# 3_InfoPerif.net
KiCad netlist of a schematic drawn in Altium Designer
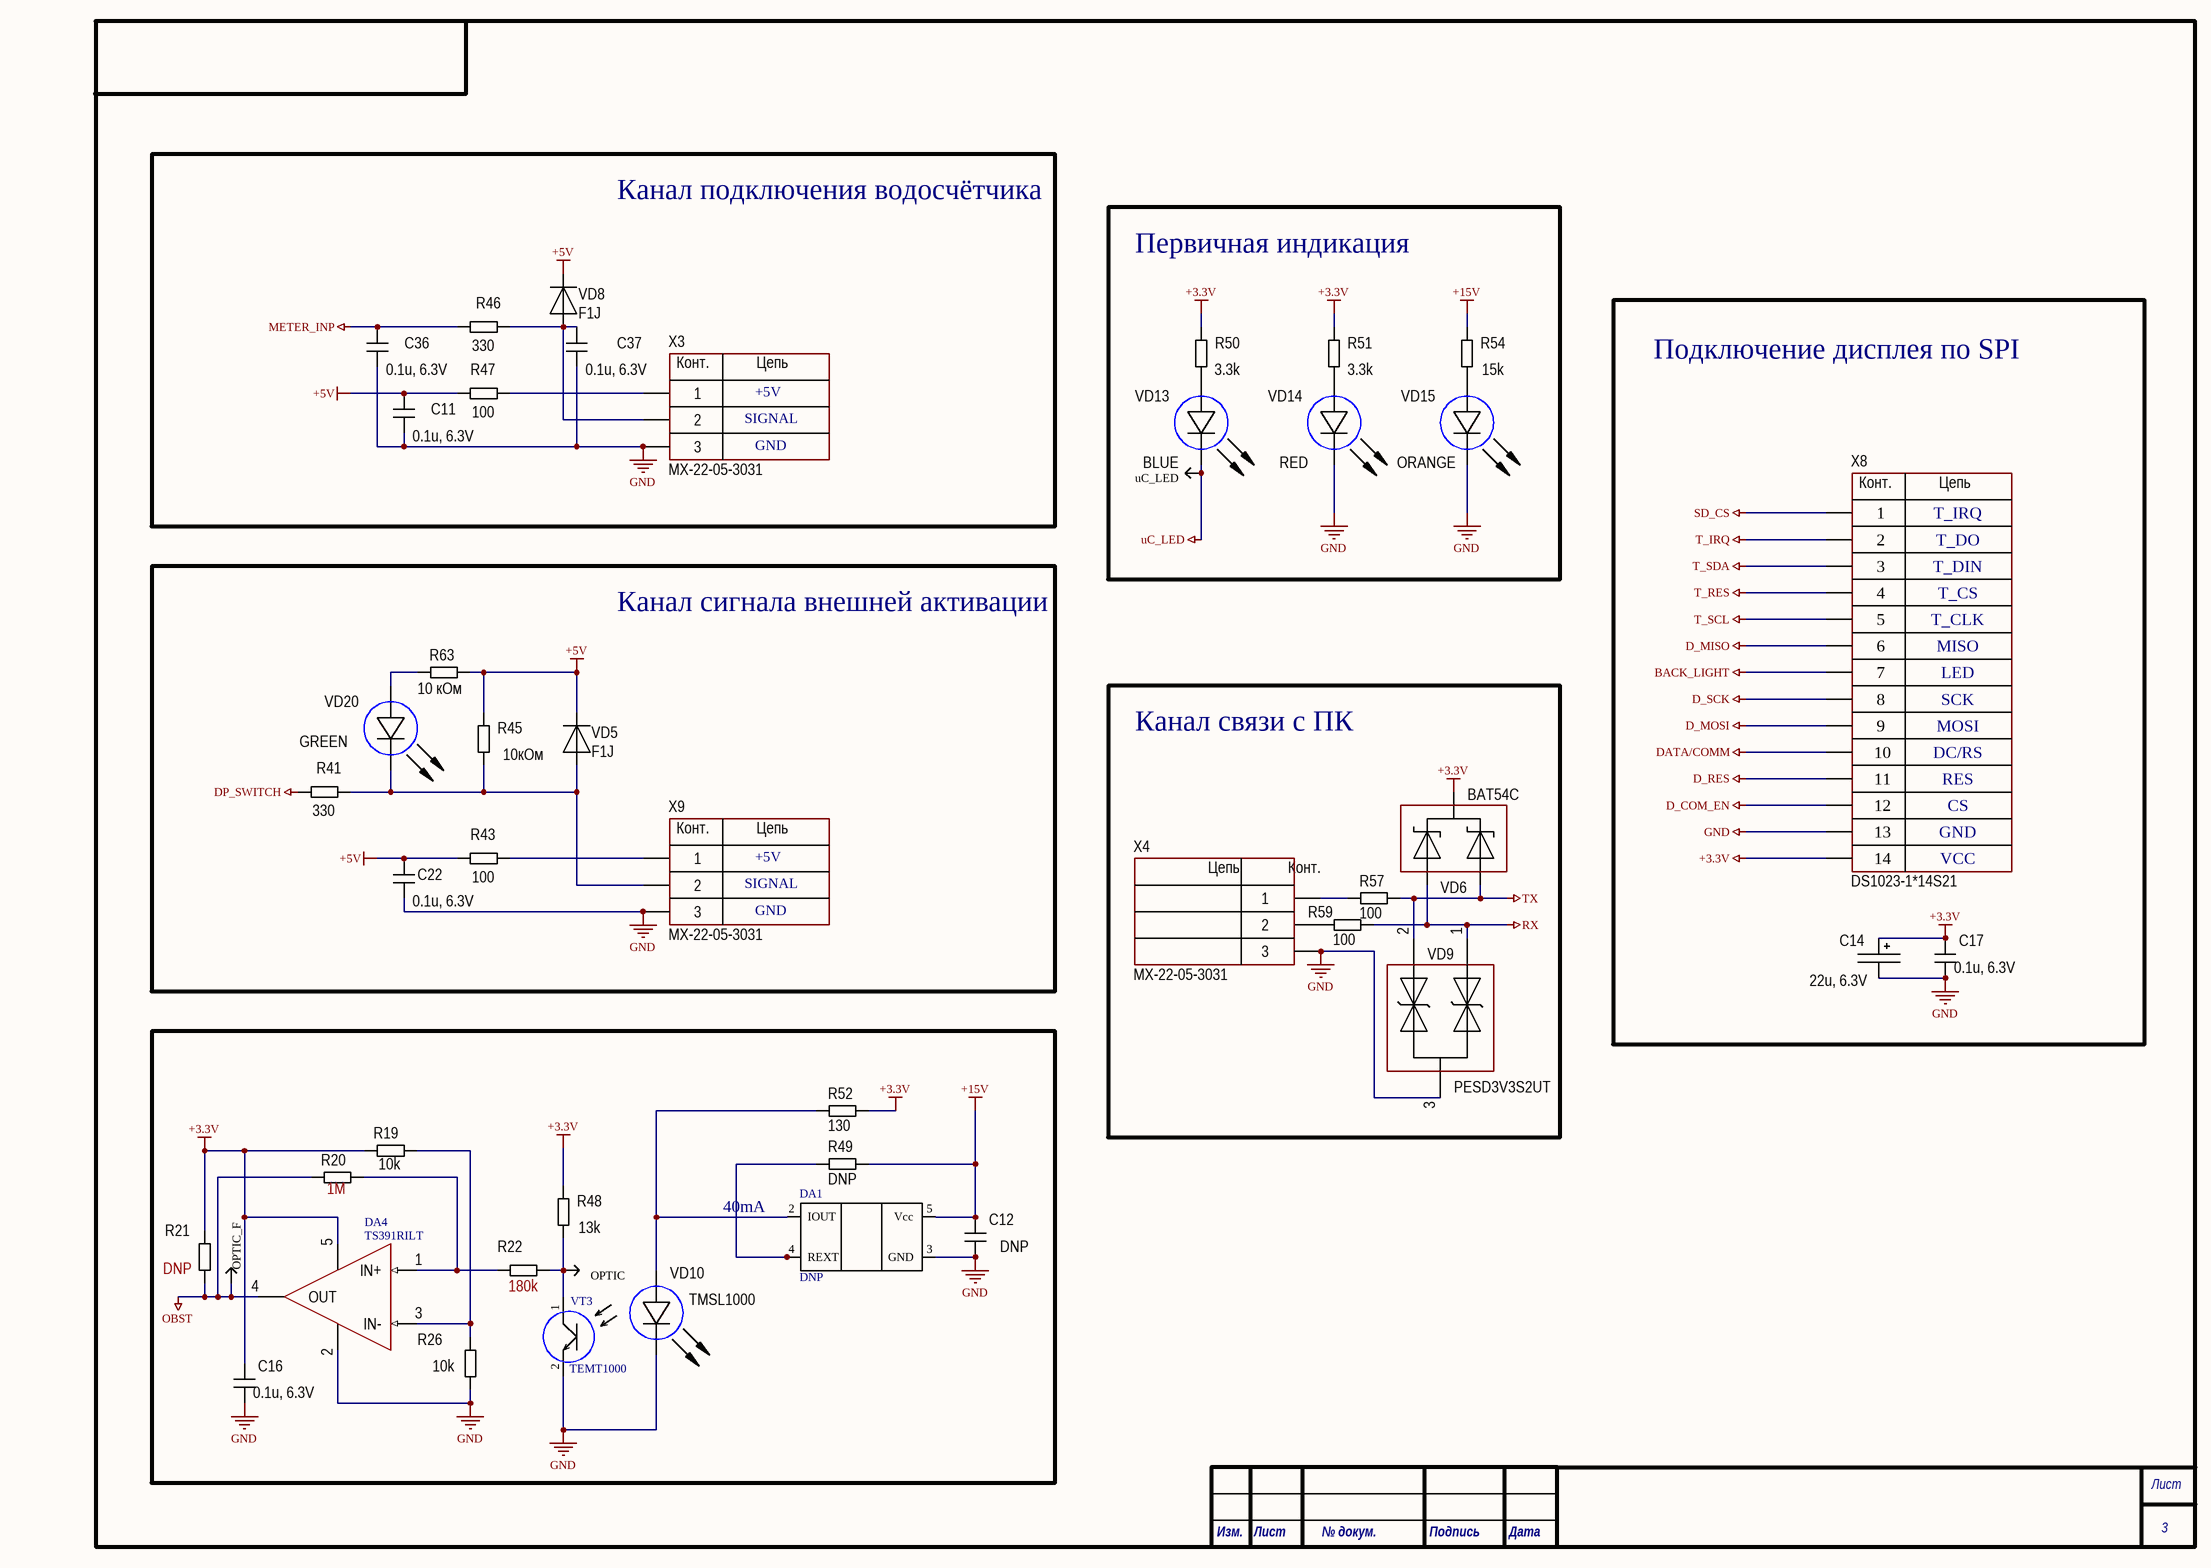
[diagram p0: 3_InfoPerif.SchDoc]

(export (version "E")
  (design (tool "Eeschema 10.0.6"))
  (components
    (comp (ref "C11")
      (value "0.1u, 6.3V")
      (footprint "CH0603C")
      (description "0805")
      (libsource (lib "Condensators") (part "Capacitor"))
    )
    (comp (ref "C12")
      (value "DNP")
      (footprint "CH0402C")
      (description "0805")
      (libsource (lib "Condensators") (part "Capacitor"))
    )
    (comp (ref "C14")
      (value "22u, 6.3V")
      (footprint "TANTAL_A")
      (libsource (lib "Condensators") (part "TantalCap"))
    )
    (comp (ref "C16")
      (value "0.1u, 6.3V")
      (footprint "CH0402C")
      (description "0805")
      (libsource (lib "Condensators") (part "Capacitor"))
    )
    (comp (ref "C17")
      (value "0.1u, 6.3V")
      (footprint "CH0402C")
      (libsource (lib "Condensators") (part "Capacitor"))
    )
    (comp (ref "C22")
      (value "0.1u, 6.3V")
      (footprint "CH0402C")
      (description "0805")
      (libsource (lib "Condensators") (part "Capacitor"))
    )
    (comp (ref "C36")
      (value "0.1u, 6.3V")
      (footprint "CH0402C")
      (description "0805")
      (libsource (lib "Condensators") (part "Capacitor"))
    )
    (comp (ref "C37")
      (value "0.1u, 6.3V")
      (footprint "CH0402C")
      (description "0805")
      (libsource (lib "Condensators") (part "Capacitor"))
    )
    (comp (ref "DA1")
      (value "DNP")
      (footprint "SOT353")
      (description "Iout = 0.617/Rext + 15 µA")
      (libsource (lib "MicroIC") (part "PSSI2021SAY"))
    )
    (comp (ref "DA4")
      (value "TS391RILT")
      (footprint "SOT23-5")
      (description "SOT23-5")
      (libsource (lib "MicroIC") (part "LMV331M5"))
    )
    (comp (ref "OPTIC") (value "~") (footprint "TestPoint") (libsource (lib "Melochi") (part "TestPoint")))
    (comp (ref "OPTIC_F") (value "~") (footprint "TestPoint") (libsource (lib "Melochi") (part "TestPoint")))
    (comp (ref "R19") (value "10k") (footprint "CH0402R") (libsource (lib "Resistors") (part "Resistor")))
    (comp (ref "R20") (value "1M") (footprint "CH0402R") (libsource (lib "Resistors") (part "Resistor")))
    (comp (ref "R21") (value "DNP") (footprint "CH0402R") (libsource (lib "Resistors") (part "Resistor")))
    (comp (ref "R22") (value "180k") (footprint "CH0402R") (libsource (lib "Resistors") (part "Resistor")))
    (comp (ref "R26") (value "10k") (footprint "CH0402R") (libsource (lib "Resistors") (part "Resistor")))
    (comp (ref "R41") (value "330") (footprint "CH0402R") (libsource (lib "Resistors") (part "Resistor")))
    (comp (ref "R43") (value "100") (footprint "CH0805R") (libsource (lib "Resistors") (part "Resistor")))
    (comp (ref "R45") (value "10кОм") (footprint "CH0603R") (libsource (lib "Resistors") (part "Resistor")))
    (comp (ref "R46") (value "330") (footprint "CH0402R") (libsource (lib "Resistors") (part "Resistor")))
    (comp (ref "R47") (value "100") (footprint "CH0805R") (libsource (lib "Resistors") (part "Resistor")))
    (comp (ref "R48")
      (value "13k")
      (footprint "CH0402R")
      (description "0805")
      (libsource (lib "Resistors") (part "Resistor"))
    )
    (comp (ref "R49")
      (value "DNP")
      (footprint "CH0805R")
      (description "0805")
      (libsource (lib "Resistors") (part "Resistor"))
    )
    (comp (ref "R50") (value "3.3k") (footprint "CH0805R") (libsource (lib "Resistors") (part "Resistor")))
    (comp (ref "R51") (value "3.3k") (footprint "CH0805R") (libsource (lib "Resistors") (part "Resistor")))
    (comp (ref "R52")
      (value "130")
      (footprint "CH0805R")
      (description "0805")
      (libsource (lib "Resistors") (part "Resistor"))
    )
    (comp (ref "R54") (value "15k") (footprint "CH0805R") (libsource (lib "Resistors") (part "Resistor")))
    (comp (ref "R57") (value "100") (footprint "CH0402R") (libsource (lib "Resistors") (part "Resistor")))
    (comp (ref "R59") (value "100") (footprint "CH0402R") (libsource (lib "Resistors") (part "Resistor")))
    (comp (ref "R63") (value "10 кОм") (footprint "CH0805R") (libsource (lib "Resistors") (part "Resistor")))
    (comp (ref "uC_LED") (value "~") (footprint "TestPoint") (libsource (lib "Melochi") (part "TestPoint")))
    (comp (ref "VD5") (value "F1J") (footprint "SOD123F") (libsource (lib "Diods") (part "Diod")))
    (comp (ref "VD6")
      (value "BAT54C")
      (footprint "SOT23_123")
      (libsource (lib "Diods") (part "Diod Schottky Array v.1"))
    )
    (comp (ref "VD8") (value "F1J") (footprint "SOD123F") (libsource (lib "Diods") (part "Diod")))
    (comp (ref "VD9")
      (value "PESD3V3S2UT")
      (footprint "SOT23_132")
      (libsource (lib "Diods") (part "TVS Array"))
    )
    (comp (ref "VD10") (value "TMSL1000") (footprint "TSML1000") (libsource (lib "Diods") (part "LED_1")))
    (comp (ref "VD13") (value "BLUE") (footprint "CH0603LB") (libsource (lib "Diods") (part "LED_1")))
    (comp (ref "VD14") (value "RED") (footprint "CH0603LB") (libsource (lib "Diods") (part "LED_1")))
    (comp (ref "VD15") (value "ORANGE") (footprint "CH0603LB") (libsource (lib "Diods") (part "LED_1")))
    (comp (ref "VD20") (value "GREEN") (footprint "CH0603LB") (libsource (lib "Diods") (part "LED_1")))
    (comp (ref "VT3")
      (value "TEMT1000")
      (footprint "TEMT1000")
      (libsource (lib "Tranzistor") (part "TEMT1000"))
    )
    (comp (ref "X3")
      (value "MX-22-05-3031")
      (footprint "CON: MX-22-05-3031")
      (libsource (lib "Connectors") (part "3-Connector"))
    )
    (comp (ref "X4")
      (value "MX-22-05-3031")
      (footprint "CON: MX-22-05-3031")
      (libsource (lib "") (part "3-Connector_1"))
    )
    (comp (ref "X8")
      (value "DS1023-1*14S21")
      (footprint "DS1024-14")
      (libsource (lib "Connectors") (part "14-Connector"))
    )
    (comp (ref "X9")
      (value "MX-22-05-3031")
      (footprint "CON: MX-22-05-3031")
      (libsource (lib "Connectors") (part "3-Connector"))
    )
  )
  (nets
    (net (code "1") (name "+3.3V") (class "Default")
      (node (ref "C14") (pin "1") (pinfunction "1_1") (pintype "power_in"))
      (node (ref "C16") (pin "2") (pinfunction "2_2") (pintype "passive"))
      (node (ref "C17") (pin "2") (pinfunction "2_2") (pintype "passive"))
      (node (ref "DA4") (pin "5") (pinfunction "V+_5") (pintype "power_in"))
      (node (ref "R19") (pin "2") (pinfunction "2_2") (pintype "passive"))
      (node (ref "R21") (pin "2") (pinfunction "2_2") (pintype "passive"))
      (node (ref "R48") (pin "2") (pinfunction "2_2") (pintype "passive"))
      (node (ref "R50") (pin "2") (pinfunction "2_2") (pintype "passive"))
      (node (ref "R51") (pin "2") (pinfunction "2_2") (pintype "passive"))
      (node (ref "R52") (pin "2") (pinfunction "2_2") (pintype "passive"))
      (node (ref "VD6") (pin "2") (pinfunction "2_2") (pintype "passive"))
      (node (ref "X8") (pin "14") (pinfunction "14_14") (pintype "power_in"))
    )
    (net (code "2") (name "+5V") (class "Default")
      (node (ref "C11") (pin "2") (pinfunction "2_2") (pintype "passive"))
      (node (ref "C22") (pin "2") (pinfunction "2_2") (pintype "passive"))
      (node (ref "R43") (pin "1") (pinfunction "1_1") (pintype "passive"))
      (node (ref "R45") (pin "1") (pinfunction "1_1") (pintype "passive"))
      (node (ref "R47") (pin "1") (pinfunction "1_1") (pintype "passive"))
      (node (ref "R63") (pin "2") (pinfunction "2_2") (pintype "passive"))
      (node (ref "VD5") (pin "2") (pinfunction "2_2") (pintype "passive"))
      (node (ref "VD8") (pin "2") (pinfunction "2_2") (pintype "passive"))
    )
    (net (code "3") (name "+15V") (class "Default")
      (node (ref "C12") (pin "2") (pinfunction "2_2") (pintype "passive"))
      (node (ref "DA1") (pin "5") (pinfunction "Vcc_5") (pintype "passive"))
      (node (ref "R49") (pin "2") (pinfunction "2_2") (pintype "passive"))
      (node (ref "R54") (pin "2") (pinfunction "2_2") (pintype "passive"))
    )
    (net (code "4") (name "BACK_LIGHT") (class "Default")
      (node (ref "X8") (pin "7") (pinfunction "7_7") (pintype "power_in"))
    )
    (net (code "5") (name "DATA{slash}COMM") (class "Default")
      (node (ref "X8") (pin "10") (pinfunction "10_10") (pintype "power_in"))
    )
    (net (code "6") (name "DP_SWITCH") (class "Default")
      (node (ref "R41") (pin "1") (pinfunction "1_1") (pintype "passive"))
    )
    (net (code "7") (name "D_COM_EN") (class "Default")
      (node (ref "X8") (pin "12") (pinfunction "12_12") (pintype "power_in"))
    )
    (net (code "8") (name "D_MISO") (class "Default")
      (node (ref "X8") (pin "6") (pinfunction "6_6") (pintype "power_in"))
    )
    (net (code "9") (name "D_MOSI") (class "Default")
      (node (ref "X8") (pin "9") (pinfunction "9_9") (pintype "power_in"))
    )
    (net (code "10") (name "D_RES") (class "Default")
      (node (ref "X8") (pin "11") (pinfunction "11_11") (pintype "power_in"))
    )
    (net (code "11") (name "D_SCK") (class "Default")
      (node (ref "X8") (pin "8") (pinfunction "8_8") (pintype "power_in"))
    )
    (net (code "12") (name "GND") (class "Default")
      (node (ref "C11") (pin "1") (pinfunction "1_1") (pintype "passive"))
      (node (ref "C12") (pin "1") (pinfunction "1_1") (pintype "passive"))
      (node (ref "C14") (pin "2") (pinfunction "2_2") (pintype "power_in"))
      (node (ref "C16") (pin "1") (pinfunction "1_1") (pintype "passive"))
      (node (ref "C17") (pin "1") (pinfunction "1_1") (pintype "passive"))
      (node (ref "C22") (pin "1") (pinfunction "1_1") (pintype "passive"))
      (node (ref "C36") (pin "1") (pinfunction "1_1") (pintype "passive"))
      (node (ref "C37") (pin "1") (pinfunction "1_1") (pintype "passive"))
      (node (ref "DA1") (pin "3") (pinfunction "GND_3") (pintype "passive"))
      (node (ref "DA4") (pin "2") (pinfunction "V-_2") (pintype "power_in"))
      (node (ref "R26") (pin "1") (pinfunction "1_1") (pintype "passive"))
      (node (ref "VD10") (pin "2") (pinfunction "C_2") (pintype "passive"))
      (node (ref "VD14") (pin "2") (pinfunction "C_2") (pintype "passive"))
      (node (ref "VD15") (pin "2") (pinfunction "C_2") (pintype "passive"))
      (node (ref "VD9") (pin "3") (pintype "passive"))
      (node (ref "VT3") (pin "2") (pinfunction "2_2") (pintype "passive"))
      (node (ref "X3") (pin "3") (pinfunction "3_3") (pintype "passive"))
      (node (ref "X4") (pin "3") (pinfunction "3_3") (pintype "passive"))
      (node (ref "X8") (pin "13") (pinfunction "13_13") (pintype "power_in"))
      (node (ref "X9") (pin "3") (pinfunction "3_3") (pintype "passive"))
    )
    (net (code "13") (name "METER_INP") (class "Default")
      (node (ref "C36") (pin "2") (pinfunction "2_2") (pintype "passive"))
      (node (ref "R46") (pin "1") (pinfunction "1_1") (pintype "passive"))
    )
    (net (code "14") (name "Net-(C37-Pad2)") (class "Default")
      (node (ref "C37") (pin "2") (pinfunction "2_2") (pintype "passive"))
      (node (ref "R46") (pin "2") (pinfunction "2_2") (pintype "passive"))
      (node (ref "VD8") (pin "1") (pinfunction "1_1") (pintype "passive"))
      (node (ref "X3") (pin "2") (pinfunction "2_2") (pintype "passive"))
    )
    (net (code "15") (name "Net-(DA1-IOUT)") (class "Default")
      (node (ref "DA1") (pin "2") (pinfunction "IOUT_2") (pintype "passive"))
      (node (ref "R52") (pin "1") (pinfunction "1_1") (pintype "passive"))
      (node (ref "VD10") (pin "1") (pinfunction "A_1") (pintype "passive"))
    )
    (net (code "16") (name "Net-(DA1-REXT)") (class "Default")
      (node (ref "DA1") (pin "4") (pinfunction "REXT_4") (pintype "passive"))
      (node (ref "R49") (pin "1") (pinfunction "1_1") (pintype "passive"))
    )
    (net (code "17") (name "Net-(DA4-IN+)") (class "Default")
      (node (ref "DA4") (pin "1") (pinfunction "IN+_1") (pintype "input"))
      (node (ref "R20") (pin "1") (pinfunction "1_1") (pintype "passive"))
      (node (ref "R22") (pin "2") (pinfunction "2_2") (pintype "passive"))
    )
    (net (code "18") (name "Net-(DA4-IN-)") (class "Default")
      (node (ref "DA4") (pin "3") (pinfunction "IN-_3") (pintype "input"))
      (node (ref "R19") (pin "1") (pinfunction "1_1") (pintype "passive"))
      (node (ref "R26") (pin "2") (pinfunction "2_2") (pintype "passive"))
    )
    (net (code "19") (name "Net-(OPTIC-Pad0)") (class "Default")
      (node (ref "OPTIC") (pin "0") (pinfunction "0_0") (pintype "passive"))
      (node (ref "R22") (pin "1") (pinfunction "1_1") (pintype "passive"))
      (node (ref "R48") (pin "1") (pinfunction "1_1") (pintype "passive"))
      (node (ref "VT3") (pin "1") (pinfunction "1_1") (pintype "passive"))
    )
    (net (code "20") (name "Net-(R43-Pad2)") (class "Default")
      (node (ref "R43") (pin "2") (pinfunction "2_2") (pintype "passive"))
      (node (ref "X9") (pin "1") (pinfunction "1_1") (pintype "passive"))
    )
    (net (code "21") (name "Net-(R47-Pad2)") (class "Default")
      (node (ref "R47") (pin "2") (pinfunction "2_2") (pintype "passive"))
      (node (ref "X3") (pin "1") (pinfunction "1_1") (pintype "passive"))
    )
    (net (code "22") (name "Net-(R57-Pad1)") (class "Default")
      (node (ref "R57") (pin "1") (pinfunction "1_1") (pintype "passive"))
      (node (ref "X4") (pin "1") (pinfunction "1_1") (pintype "passive"))
    )
    (net (code "23") (name "Net-(R59-Pad1)") (class "Default")
      (node (ref "R59") (pin "1") (pinfunction "1_1") (pintype "passive"))
      (node (ref "X4") (pin "2") (pinfunction "2_2") (pintype "passive"))
    )
    (net (code "24") (name "Net-(VD13-A)") (class "Default")
      (node (ref "R50") (pin "1") (pinfunction "1_1") (pintype "passive"))
      (node (ref "VD13") (pin "1") (pinfunction "A_1") (pintype "passive"))
    )
    (net (code "25") (name "Net-(VD14-A)") (class "Default")
      (node (ref "R51") (pin "1") (pinfunction "1_1") (pintype "passive"))
      (node (ref "VD14") (pin "1") (pinfunction "A_1") (pintype "passive"))
    )
    (net (code "26") (name "Net-(VD15-A)") (class "Default")
      (node (ref "R54") (pin "1") (pinfunction "1_1") (pintype "passive"))
      (node (ref "VD15") (pin "1") (pinfunction "A_1") (pintype "passive"))
    )
    (net (code "27") (name "Net-(VD20-A)") (class "Default")
      (node (ref "R63") (pin "1") (pinfunction "1_1") (pintype "passive"))
      (node (ref "VD20") (pin "1") (pinfunction "A_1") (pintype "passive"))
    )
    (net (code "28") (name "Net-(VD20-C)") (class "Default")
      (node (ref "R41") (pin "2") (pinfunction "2_2") (pintype "passive"))
      (node (ref "R45") (pin "2") (pinfunction "2_2") (pintype "passive"))
      (node (ref "VD20") (pin "2") (pinfunction "C_2") (pintype "passive"))
      (node (ref "VD5") (pin "1") (pinfunction "1_1") (pintype "passive"))
      (node (ref "X9") (pin "2") (pinfunction "2_2") (pintype "passive"))
    )
    (net (code "29") (name "OBST") (class "Default")
      (node (ref "DA4") (pin "4") (pinfunction "OUT_4") (pintype "power_in"))
      (node (ref "OPTIC_F") (pin "0") (pinfunction "0_0") (pintype "passive"))
      (node (ref "R20") (pin "2") (pinfunction "2_2") (pintype "passive"))
      (node (ref "R21") (pin "1") (pinfunction "1_1") (pintype "passive"))
    )
    (net (code "30") (name "RX") (class "Default")
      (node (ref "R59") (pin "2") (pinfunction "2_2") (pintype "passive"))
      (node (ref "VD6") (pin "3") (pinfunction "3_3") (pintype "passive"))
      (node (ref "VD9") (pin "1") (pintype "passive"))
    )
    (net (code "31") (name "SD_CS") (class "Default")
      (node (ref "X8") (pin "1") (pinfunction "1_1") (pintype "passive"))
    )
    (net (code "32") (name "TX") (class "Default")
      (node (ref "R57") (pin "2") (pinfunction "2_2") (pintype "passive"))
      (node (ref "VD6") (pin "1") (pinfunction "1_1") (pintype "passive"))
      (node (ref "VD9") (pin "2") (pintype "passive"))
    )
    (net (code "33") (name "T_IRQ") (class "Default")
      (node (ref "X8") (pin "2") (pinfunction "2_2") (pintype "passive"))
    )
    (net (code "34") (name "T_RES") (class "Default")
      (node (ref "X8") (pin "4") (pinfunction "4_4") (pintype "power_in"))
    )
    (net (code "35") (name "T_SCL") (class "Default")
      (node (ref "X8") (pin "5") (pinfunction "5_5") (pintype "power_in"))
    )
    (net (code "36") (name "T_SDA") (class "Default")
      (node (ref "X8") (pin "3") (pinfunction "3_3") (pintype "power_in"))
    )
    (net (code "37") (name "uC_LED") (class "Default")
      (node (ref "VD13") (pin "2") (pinfunction "C_2") (pintype "passive"))
      (node (ref "uC_LED") (pin "0") (pinfunction "0_0") (pintype "passive"))
    )
  )
)
